# InputConnectors.net
KiCad netlist of a schematic drawn in Altium Designer
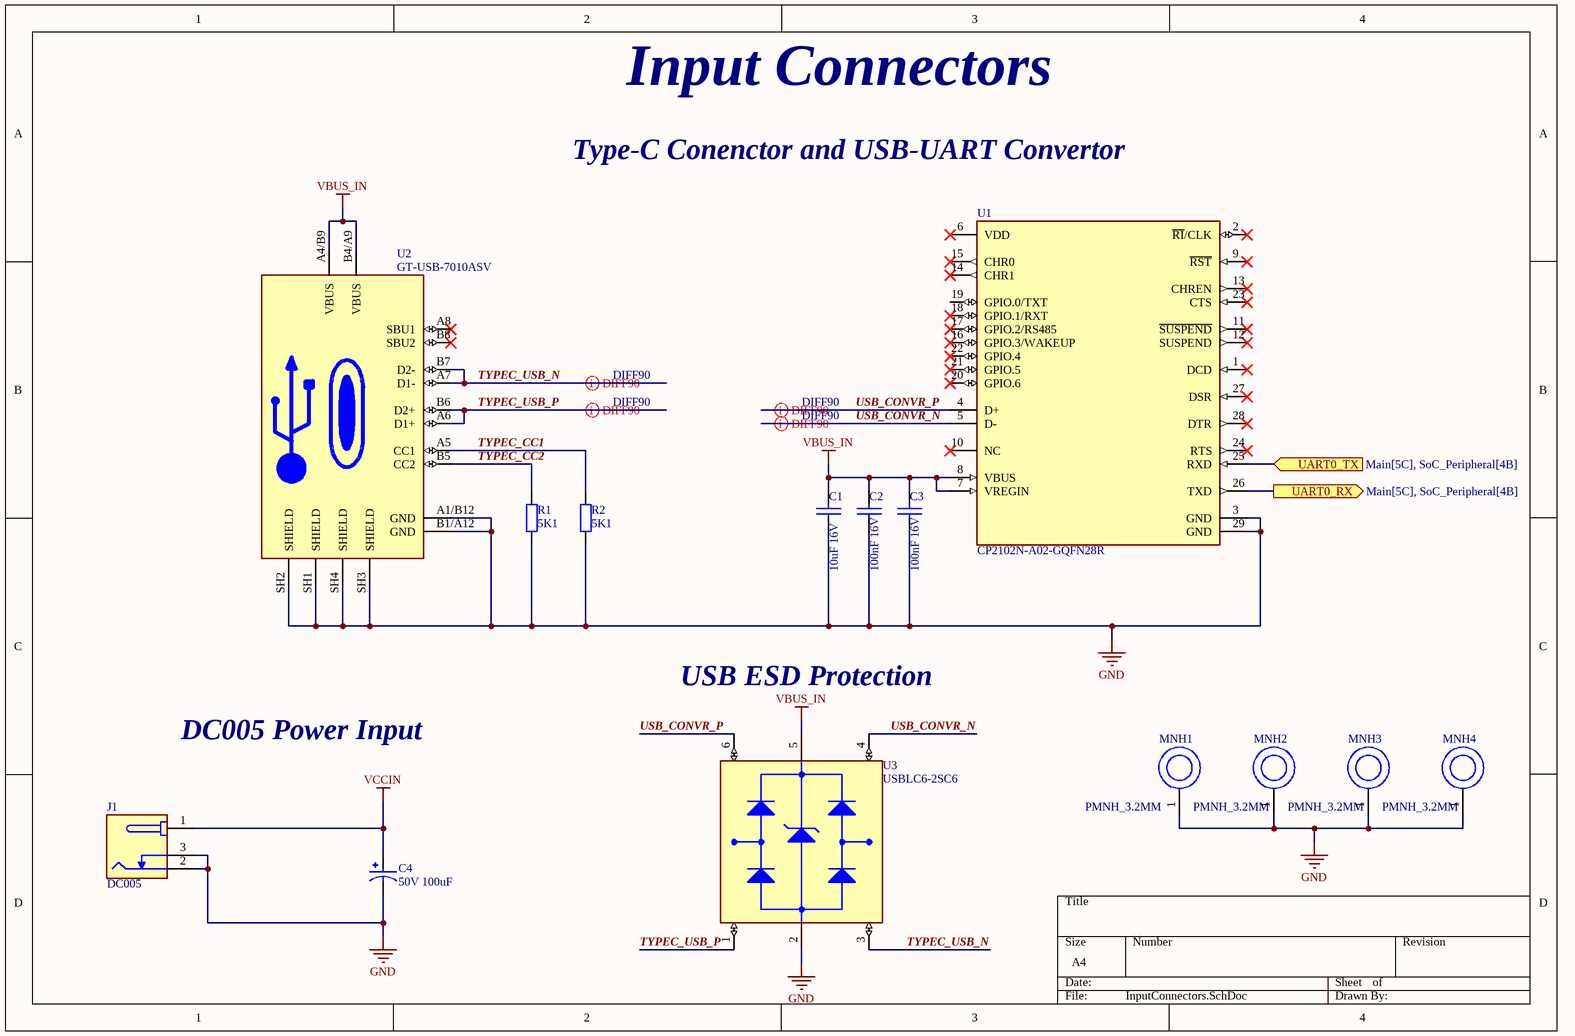
[diagram p0: InputConnectors.SchDoc]

(export (version "E")
  (design (tool "Eeschema 10.0.6"))
  (components
    (comp (ref "C1")
      (value "10uF 16V")
      (footprint "C_0603")
      (description "Capacitor 0603 SMD")
      (libsource (lib "tor1kkLib") (part "C_0603"))
    )
    (comp (ref "C2")
      (value "100nF 16V")
      (footprint "C_0402")
      (description "Capacitor 0402 SMD")
      (libsource (lib "tor1kkLib") (part "C_0402"))
    )
    (comp (ref "C3")
      (value "100nF 16V")
      (footprint "C_0402")
      (description "Capacitor 0402 SMD")
      (libsource (lib "tor1kkLib") (part "C_0402"))
    )
    (comp (ref "C4")
      (value "50V 100uF")
      (footprint "CAP_D6.3xL7.7mm")
      (description "100uF 50V 229mA@120Hz ±20% SMD,D6.3xL7.7mm Aluminum Electrolytic Capacitors - SMD ROHS")
      (fields (field (name "MANUFACTURER PART NUMBER") "RVT1H101M0607"))
      (libsource (lib "tor1kkLib") (part "RVT1H101M0607"))
    )
    (comp (ref "J1")
      (value "DC005")
      (footprint "DC005")
      (description "Bend-in DC Power Receptacle -20℃~+70℃ 2mm 6.3mm 5A 24V Plugin DC Power Connectors ROHS")
      (libsource (lib "tor1kkLib") (part "DC005"))
    )
    (comp (ref "MNH1")
      (value "PMNH_3.2MM")
      (footprint "PMNH_3.2MM")
      (libsource (lib "tor1kkLib") (part "PMNH_3.2MM"))
    )
    (comp (ref "MNH2")
      (value "PMNH_3.2MM")
      (footprint "PMNH_3.2MM")
      (libsource (lib "tor1kkLib") (part "PMNH_3.2MM"))
    )
    (comp (ref "MNH3")
      (value "PMNH_3.2MM")
      (footprint "PMNH_3.2MM")
      (libsource (lib "tor1kkLib") (part "PMNH_3.2MM"))
    )
    (comp (ref "MNH4")
      (value "PMNH_3.2MM")
      (footprint "PMNH_3.2MM")
      (libsource (lib "tor1kkLib") (part "PMNH_3.2MM"))
    )
    (comp (ref "R1")
      (value "5K1")
      (footprint "R_0603")
      (description "Resistor 0603 SMD")
      (libsource (lib "tor1kkLib") (part "R_0603"))
    )
    (comp (ref "R2")
      (value "5K1")
      (footprint "R_0603")
      (description "Resistor 0603 SMD")
      (libsource (lib "tor1kkLib") (part "R_0603"))
    )
    (comp (ref "U1")
      (value "CP2102N-A02-GQFN28R")
      (footprint "FP-CP2102N-A02-GQFN28R-MFG")
      (description "IC USB TO UART BRIDGE QFN28")
      (libsource (lib "Altium Content Vault") (part "670edaef084fb69d2a747396d70a05e"))
    )
    (comp (ref "U2")
      (value "GT-USB-7010ASV")
      (footprint "GT-USB-7010ASV")
      (description "USB 2.0 3A 1 Horizontal attachment 16P Female -40℃~+85℃ Type-C SMD USB Connectors ROHS")
      (fields (field (name "MANUFACTURER") "G-Switch"))
      (libsource (lib "tor1kkLib") (part "GT-USB-7010ASV"))
    )
    (comp (ref "U3")
      (value "USBLC6-2SC6")
      (footprint "SOT-23-6")
      (description "6A 12V 150W 6V Unidirectional 5V SOT-23-6 ESD and Surge Protection (TVS/ESD) ROHS")
      (fields (field (name "MANUFACTURER") "STMicroelectronics"))
      (libsource (lib "tor1kkLib") (part "USBLC6-2SC6"))
    )
  )
  (nets
    (net (code "1") (name "/TYPEC_CC1") (class "Default")
      (node (ref "R2") (pin "2") (pintype "passive"))
      (node (ref "U2") (pin "A5") (pinfunction "CC1_A5") (pintype "bidirectional"))
    )
    (net (code "2") (name "/TYPEC_CC2") (class "Default")
      (node (ref "R1") (pin "2") (pintype "passive"))
      (node (ref "U2") (pin "B5") (pinfunction "CC2_B5") (pintype "bidirectional"))
    )
    (net (code "3") (name "/TYPEC_USB_N") (class "Default")
      (node (ref "U2") (pin "A7") (pinfunction "D1-_A7") (pintype "bidirectional"))
      (node (ref "U2") (pin "B7") (pinfunction "D2-_B7") (pintype "bidirectional"))
      (node (ref "U3") (pin "3") (pinfunction "I/O2_IN_3") (pintype "bidirectional"))
    )
    (net (code "4") (name "/TYPEC_USB_P") (class "Default")
      (node (ref "U2") (pin "A6") (pinfunction "D1+_A6") (pintype "bidirectional"))
      (node (ref "U2") (pin "B6") (pinfunction "D2+_B6") (pintype "bidirectional"))
      (node (ref "U3") (pin "1") (pinfunction "I/O1_IN_1") (pintype "bidirectional"))
    )
    (net (code "5") (name "/UART0_RX") (class "Default")
      (node (ref "U1") (pin "26") (pinfunction "TXD_26") (pintype "output"))
    )
    (net (code "6") (name "/UART0_TX") (class "Default")
      (node (ref "U1") (pin "25") (pinfunction "RXD_25") (pintype "input"))
    )
    (net (code "7") (name "/USB_CONVR_N") (class "Default")
      (node (ref "U1") (pin "5") (pinfunction "D-_5") (pintype "passive"))
      (node (ref "U3") (pin "4") (pinfunction "I/O2_OUT_4") (pintype "bidirectional"))
    )
    (net (code "8") (name "/USB_CONVR_P") (class "Default")
      (node (ref "U1") (pin "4") (pinfunction "D+_4") (pintype "passive"))
      (node (ref "U3") (pin "6") (pinfunction "I/O1_OUT_6") (pintype "bidirectional"))
    )
    (net (code "9") (name "GND") (class "Default")
      (node (ref "C1") (pin "2") (pintype "passive"))
      (node (ref "C2") (pin "2") (pintype "passive"))
      (node (ref "C3") (pin "2") (pintype "passive"))
      (node (ref "C4") (pin "2") (pinfunction "2_2") (pintype "passive"))
      (node (ref "J1") (pin "2") (pinfunction "2_2") (pintype "passive"))
      (node (ref "J1") (pin "3") (pinfunction "3_3") (pintype "passive"))
      (node (ref "MNH1") (pin "1") (pinfunction "1_1") (pintype "passive"))
      (node (ref "MNH2") (pin "1") (pinfunction "1_1") (pintype "passive"))
      (node (ref "MNH3") (pin "1") (pinfunction "1_1") (pintype "passive"))
      (node (ref "MNH4") (pin "1") (pinfunction "1_1") (pintype "passive"))
      (node (ref "R1") (pin "1") (pintype "passive"))
      (node (ref "R2") (pin "1") (pintype "passive"))
      (node (ref "U1") (pin "29") (pinfunction "GND_29") (pintype "power_in"))
      (node (ref "U1") (pin "3") (pinfunction "GND_3") (pintype "power_in"))
      (node (ref "U2") (pin "A1/B12") (pinfunction "GND_A1/B12") (pintype "power_in"))
      (node (ref "U2") (pin "B1/A12") (pinfunction "GND_B1/A12") (pintype "power_in"))
      (node (ref "U2") (pin "SH1") (pinfunction "SHIELD_SH1") (pintype "passive"))
      (node (ref "U2") (pin "SH2") (pinfunction "SHIELD_SH2") (pintype "passive"))
      (node (ref "U2") (pin "SH3") (pinfunction "SHIELD_SH3") (pintype "passive"))
      (node (ref "U2") (pin "SH4") (pinfunction "SHIELD_SH4") (pintype "passive"))
      (node (ref "U3") (pin "2") (pinfunction "GND_2") (pintype "power_in"))
    )
    (net (code "10") (name "VBUS_IN") (class "Default")
      (node (ref "C1") (pin "1") (pintype "passive"))
      (node (ref "C2") (pin "1") (pintype "passive"))
      (node (ref "C3") (pin "1") (pintype "passive"))
      (node (ref "U1") (pin "7") (pinfunction "VREGIN_7") (pintype "input"))
      (node (ref "U1") (pin "8") (pinfunction "VBUS_8") (pintype "input"))
      (node (ref "U2") (pin "A4/B9") (pinfunction "VBUS_A4/B9") (pintype "power_in"))
      (node (ref "U2") (pin "B4/A9") (pinfunction "VBUS_B4/A9") (pintype "power_in"))
      (node (ref "U3") (pin "5") (pinfunction "VBUS_5") (pintype "power_in"))
    )
    (net (code "11") (name "VCCIN") (class "Default")
      (node (ref "C4") (pin "1") (pinfunction "1_1") (pintype "passive"))
      (node (ref "J1") (pin "1") (pinfunction "1_1") (pintype "passive"))
    )
    (net (code "12") (name "unconnected-(U1-CHR0-Pad15)") (class "Default")
      (node (ref "U1") (pin "15") (pinfunction "CHR0_15") (pintype "output+no_connect"))
    )
    (net (code "13") (name "unconnected-(U1-CHR1-Pad14)") (class "Default")
      (node (ref "U1") (pin "14") (pinfunction "CHR1_14") (pintype "output+no_connect"))
    )
    (net (code "14") (name "unconnected-(U1-CHREN-Pad13)") (class "Default")
      (node (ref "U1") (pin "13") (pinfunction "CHREN_13") (pintype "output+no_connect"))
    )
    (net (code "15") (name "unconnected-(U1-CTS-Pad23)") (class "Default")
      (node (ref "U1") (pin "23") (pinfunction "CTS_23") (pintype "input+no_connect"))
    )
    (net (code "16") (name "unconnected-(U1-DCD-Pad1)") (class "Default")
      (node (ref "U1") (pin "1") (pinfunction "DCD_1") (pintype "input+no_connect"))
    )
    (net (code "17") (name "unconnected-(U1-DSR-Pad27)") (class "Default")
      (node (ref "U1") (pin "27") (pinfunction "DSR_27") (pintype "input+no_connect"))
    )
    (net (code "18") (name "unconnected-(U1-DTR-Pad28)") (class "Default")
      (node (ref "U1") (pin "28") (pinfunction "DTR_28") (pintype "output+no_connect"))
    )
    (net (code "19") (name "unconnected-(U1-GPIO.0{slash}TXT-Pad19)") (class "Default")
      (node (ref "U1") (pin "19") (pinfunction "GPIO.0/TXT_19") (pintype "bidirectional"))
    )
    (net (code "20") (name "unconnected-(U1-GPIO.1{slash}RXT-Pad18)") (class "Default")
      (node (ref "U1") (pin "18") (pinfunction "GPIO.1/RXT_18") (pintype "bidirectional+no_connect"))
    )
    (net (code "21") (name "unconnected-(U1-GPIO.2{slash}RS485-Pad17)") (class "Default")
      (node (ref "U1") (pin "17") (pinfunction "GPIO.2/RS485_17") (pintype "bidirectional+no_connect"))
    )
    (net (code "22") (name "unconnected-(U1-GPIO.3{slash}WAKEUP-Pad16)") (class "Default")
      (node (ref "U1") (pin "16") (pinfunction "GPIO.3/WAKEUP_16") (pintype "bidirectional+no_connect"))
    )
    (net (code "23") (name "unconnected-(U1-GPIO.4-Pad22)") (class "Default")
      (node (ref "U1") (pin "22") (pinfunction "GPIO.4_22") (pintype "bidirectional+no_connect"))
    )
    (net (code "24") (name "unconnected-(U1-GPIO.5-Pad21)") (class "Default")
      (node (ref "U1") (pin "21") (pinfunction "GPIO.5_21") (pintype "bidirectional+no_connect"))
    )
    (net (code "25") (name "unconnected-(U1-GPIO.6-Pad20)") (class "Default")
      (node (ref "U1") (pin "20") (pinfunction "GPIO.6_20") (pintype "bidirectional+no_connect"))
    )
    (net (code "26") (name "unconnected-(U1-NC-Pad10)") (class "Default")
      (node (ref "U1") (pin "10") (pinfunction "NC_10") (pintype "passive+no_connect"))
    )
    (net (code "27") (name "unconnected-(U1-RTS-Pad24)") (class "Default")
      (node (ref "U1") (pin "24") (pinfunction "RTS_24") (pintype "output+no_connect"))
    )
    (net (code "28") (name "unconnected-(U1-SUSPEND-Pad12)") (class "Default")
      (node (ref "U1") (pin "12") (pinfunction "SUSPEND_12") (pintype "output+no_connect"))
    )
    (net (code "29") (name "unconnected-(U1-VDD-Pad6)") (class "Default")
      (node (ref "U1") (pin "6") (pinfunction "VDD_6") (pintype "power_in+no_connect"))
    )
    (net (code "30") (name "unconnected-(U1-~{RI}{slash}CLK-Pad2)") (class "Default")
      (node (ref "U1") (pin "2") (pinfunction "~{RI}/CLK_2") (pintype "bidirectional+no_connect"))
    )
    (net (code "31") (name "unconnected-(U1-~{RST}-Pad9)") (class "Default")
      (node (ref "U1") (pin "9") (pinfunction "~{RST}_9") (pintype "input+no_connect"))
    )
    (net (code "32") (name "unconnected-(U1-~{SUSPEND}-Pad11)") (class "Default")
      (node (ref "U1") (pin "11") (pinfunction "~{SUSPEND}_11") (pintype "output+no_connect"))
    )
    (net (code "33") (name "unconnected-(U2-SBU1-PadA8)") (class "Default")
      (node (ref "U2") (pin "A8") (pinfunction "SBU1_A8") (pintype "bidirectional+no_connect"))
    )
    (net (code "34") (name "unconnected-(U2-SBU2-PadB8)") (class "Default")
      (node (ref "U2") (pin "B8") (pinfunction "SBU2_B8") (pintype "bidirectional+no_connect"))
    )
  )
)
